# LED.net
KiCad netlist of a schematic drawn in Altium Designer
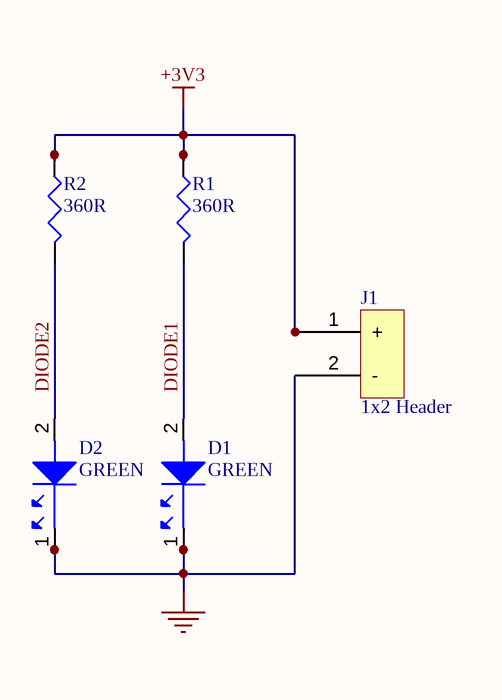
[diagram p0: LED.SchDoc]

(export (version "E")
  (design (tool "Eeschema 10.0.6"))
  (components
    (comp (ref "D1")
      (value "GREEN")
      (footprint "LED0603G")
      (description "LED SM 0603 3V -/1000/-MCD GREEN")
      (fields
        (field (name "MANUFACTURER") "Visual Communications")
        (field (name "MANUFACTURER PART NUMBER") "LSM0603453V")
      )
      (libsource (lib "LED_Schlib") (part "LSM0603453V"))
    )
    (comp (ref "D2")
      (value "GREEN")
      (footprint "LED0603G")
      (description "LED SM 0603 3V -/1000/-MCD GREEN")
      (fields
        (field (name "MANUFACTURER") "Visual Communications")
        (field (name "MANUFACTURER PART NUMBER") "LSM0603453V")
      )
      (libsource (lib "LED_Schlib") (part "LSM0603453V"))
    )
    (comp (ref "J1")
      (value "1x2 Header")
      (footprint "HDR1x2")
      (description "CONN HEADER VERT 2POS 2.54MM")
      (fields (field (name "MANUFACTURER PART NUMBER") "22-27-2021") (field (name "MANUFACTURER") "Molex"))
      (libsource (lib "LED_Schlib") (part "22-27-2021"))
    )
    (comp (ref "R1")
      (value "360R")
      (footprint "R0805")
      (description "RES SMD 360 OHM 1% 1/8W 0805")
      (fields
        (field (name "MANUFACTURER") "Yageo")
        (field (name "MANUFACTURER PART NUMBER") "AC0805FR-07360RL")
      )
      (libsource (lib "LED_Schlib") (part "AC0805FR-07360RL"))
    )
    (comp (ref "R2")
      (value "360R")
      (footprint "R0805")
      (description "RES SMD 360 OHM 1% 1/8W 0805")
      (fields
        (field (name "MANUFACTURER") "Yageo")
        (field (name "MANUFACTURER PART NUMBER") "AC0805FR-07360RL")
      )
      (libsource (lib "LED_Schlib") (part "AC0805FR-07360RL"))
    )
  )
  (nets
    (net (code "1") (name "+3V3") (class "Default")
      (node (ref "J1") (pin "1") (pinfunction "+_1") (pintype "passive"))
      (node (ref "R1") (pin "1") (pinfunction "1_1") (pintype "passive"))
      (node (ref "R2") (pin "1") (pinfunction "1_1") (pintype "passive"))
    )
    (net (code "2") (name "/DIODE1") (class "Default")
      (node (ref "D1") (pin "2") (pinfunction "2_2") (pintype "passive"))
      (node (ref "R1") (pin "2") (pinfunction "2_2") (pintype "passive"))
    )
    (net (code "3") (name "/DIODE2") (class "Default")
      (node (ref "D2") (pin "2") (pinfunction "2_2") (pintype "passive"))
      (node (ref "R2") (pin "2") (pinfunction "2_2") (pintype "passive"))
    )
    (net (code "4") (name "GND") (class "Default")
      (node (ref "D1") (pin "1") (pinfunction "1_1") (pintype "passive"))
      (node (ref "D2") (pin "1") (pinfunction "1_1") (pintype "passive"))
      (node (ref "J1") (pin "2") (pinfunction "-_2") (pintype "passive"))
    )
  )
)
